# v001.net
KiCad netlist of a schematic drawn in EAGLE
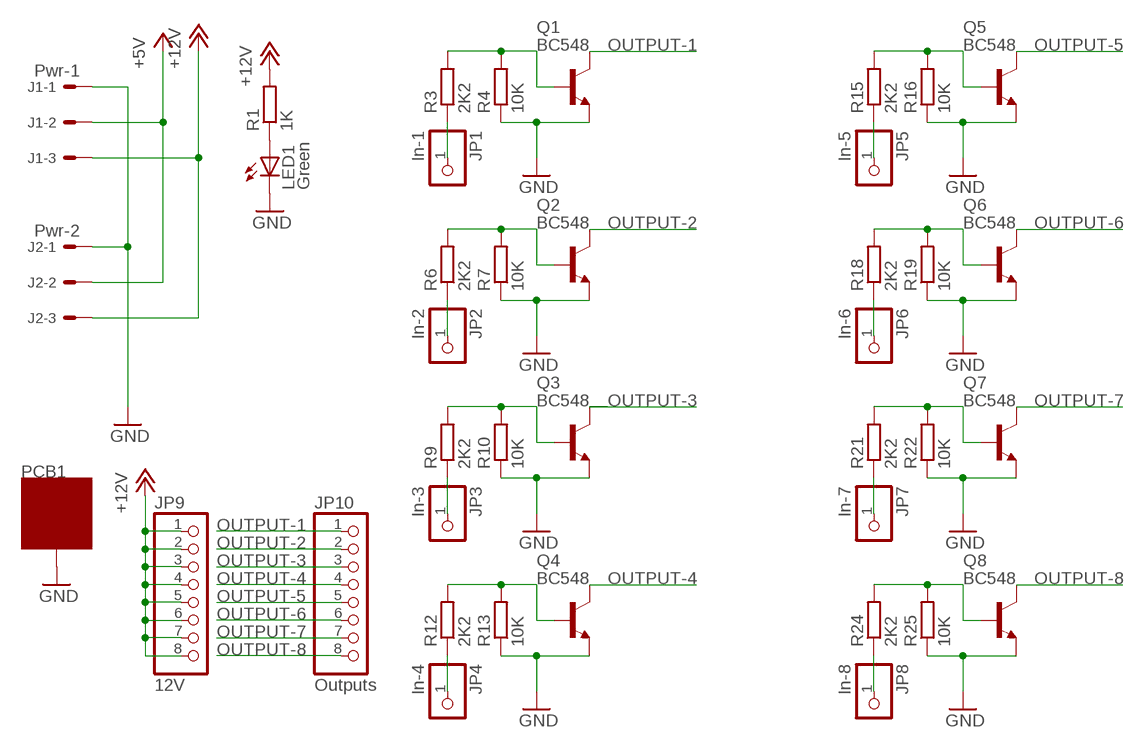
[diagram p0: schematic, sheet 1]

(export (version "E")
  (design (tool "Eeschema 10.0.6"))
  (components
    (comp (ref "J1")
      (value "Pwr-1")
      (footprint "eagle-import:6410-03")
      (libsource (lib "eagle-import") (part "22-?-0327-2031"))
    )
    (comp (ref "J2")
      (value "Pwr-2")
      (footprint "eagle-import:6410-03")
      (libsource (lib "eagle-import") (part "22-?-0327-2031"))
    )
    (comp (ref "JP1")
      (value "In-1")
      (footprint "eagle-import:1X01")
      (libsource (lib "eagle-import") (part "PINHD-1X1"))
    )
    (comp (ref "JP2")
      (value "In-2")
      (footprint "eagle-import:1X01")
      (libsource (lib "eagle-import") (part "PINHD-1X1"))
    )
    (comp (ref "JP3")
      (value "In-3")
      (footprint "eagle-import:1X01")
      (libsource (lib "eagle-import") (part "PINHD-1X1"))
    )
    (comp (ref "JP4")
      (value "In-4")
      (footprint "eagle-import:1X01")
      (libsource (lib "eagle-import") (part "PINHD-1X1"))
    )
    (comp (ref "JP5")
      (value "In-5")
      (footprint "eagle-import:1X01")
      (libsource (lib "eagle-import") (part "PINHD-1X1"))
    )
    (comp (ref "JP6")
      (value "In-6")
      (footprint "eagle-import:1X01")
      (libsource (lib "eagle-import") (part "PINHD-1X1"))
    )
    (comp (ref "JP7")
      (value "In-7")
      (footprint "eagle-import:1X01")
      (libsource (lib "eagle-import") (part "PINHD-1X1"))
    )
    (comp (ref "JP8")
      (value "In-8")
      (footprint "eagle-import:1X01")
      (libsource (lib "eagle-import") (part "PINHD-1X1"))
    )
    (comp (ref "JP9")
      (value "12V")
      (footprint "eagle-import:1X08")
      (libsource (lib "eagle-import") (part "PINHD-1X8"))
    )
    (comp (ref "JP10")
      (value "Outputs")
      (footprint "eagle-import:1X08")
      (libsource (lib "eagle-import") (part "PINHD-1X8"))
    )
    (comp (ref "LED1")
      (value "Green")
      (footprint "eagle-import:LED3MM")
      (libsource (lib "eagle-import") (part "LED3MM"))
    )
    (comp (ref "PCB1")
      (value "ZZZ_MODULE05X05")
      (footprint "eagle-import:ZZZ_MODULE_05X05")
      (libsource (lib "eagle-import") (part "ZZZ_MODULE05X05"))
    )
    (comp (ref "Q1")
      (value "BC548")
      (footprint "eagle-import:TO92-EBC")
      (libsource (lib "eagle-import") (part "BC548"))
    )
    (comp (ref "Q2")
      (value "BC548")
      (footprint "eagle-import:TO92-EBC")
      (libsource (lib "eagle-import") (part "BC548"))
    )
    (comp (ref "Q3")
      (value "BC548")
      (footprint "eagle-import:TO92-EBC")
      (libsource (lib "eagle-import") (part "BC548"))
    )
    (comp (ref "Q4")
      (value "BC548")
      (footprint "eagle-import:TO92-EBC")
      (libsource (lib "eagle-import") (part "BC548"))
    )
    (comp (ref "Q5")
      (value "BC548")
      (footprint "eagle-import:TO92-EBC")
      (libsource (lib "eagle-import") (part "BC548"))
    )
    (comp (ref "Q6")
      (value "BC548")
      (footprint "eagle-import:TO92-EBC")
      (libsource (lib "eagle-import") (part "BC548"))
    )
    (comp (ref "Q7")
      (value "BC548")
      (footprint "eagle-import:TO92-EBC")
      (libsource (lib "eagle-import") (part "BC548"))
    )
    (comp (ref "Q8")
      (value "BC548")
      (footprint "eagle-import:TO92-EBC")
      (libsource (lib "eagle-import") (part "BC548"))
    )
    (comp (ref "R1")
      (value "1K")
      (footprint "eagle-import:0207_2V")
      (libsource (lib "eagle-import") (part "resistor_R-EU_0207/2V"))
    )
    (comp (ref "R3")
      (value "2K2")
      (footprint "eagle-import:0204_7")
      (libsource (lib "eagle-import") (part "R-EU_0204/7"))
    )
    (comp (ref "R4")
      (value "10K")
      (footprint "eagle-import:0207_2V")
      (libsource (lib "eagle-import") (part "resistor_R-EU_0207/2V"))
    )
    (comp (ref "R6")
      (value "2K2")
      (footprint "eagle-import:0204_7")
      (libsource (lib "eagle-import") (part "R-EU_0204/7"))
    )
    (comp (ref "R7")
      (value "10K")
      (footprint "eagle-import:0207_2V")
      (libsource (lib "eagle-import") (part "resistor_R-EU_0207/2V"))
    )
    (comp (ref "R9")
      (value "2K2")
      (footprint "eagle-import:0204_7")
      (libsource (lib "eagle-import") (part "R-EU_0204/7"))
    )
    (comp (ref "R10")
      (value "10K")
      (footprint "eagle-import:0207_2V")
      (libsource (lib "eagle-import") (part "resistor_R-EU_0207/2V"))
    )
    (comp (ref "R12")
      (value "2K2")
      (footprint "eagle-import:0204_7")
      (libsource (lib "eagle-import") (part "R-EU_0204/7"))
    )
    (comp (ref "R13")
      (value "10K")
      (footprint "eagle-import:0207_2V")
      (libsource (lib "eagle-import") (part "resistor_R-EU_0207/2V"))
    )
    (comp (ref "R15")
      (value "2K2")
      (footprint "eagle-import:0204_7")
      (libsource (lib "eagle-import") (part "R-EU_0204/7"))
    )
    (comp (ref "R16")
      (value "10K")
      (footprint "eagle-import:0207_2V")
      (libsource (lib "eagle-import") (part "resistor_R-EU_0207/2V"))
    )
    (comp (ref "R18")
      (value "2K2")
      (footprint "eagle-import:0204_7")
      (libsource (lib "eagle-import") (part "R-EU_0204/7"))
    )
    (comp (ref "R19")
      (value "10K")
      (footprint "eagle-import:0207_2V")
      (libsource (lib "eagle-import") (part "resistor_R-EU_0207/2V"))
    )
    (comp (ref "R21")
      (value "2K2")
      (footprint "eagle-import:0204_7")
      (libsource (lib "eagle-import") (part "R-EU_0204/7"))
    )
    (comp (ref "R22")
      (value "10K")
      (footprint "eagle-import:0207_2V")
      (libsource (lib "eagle-import") (part "resistor_R-EU_0207/2V"))
    )
    (comp (ref "R24")
      (value "2K2")
      (footprint "eagle-import:0204_7")
      (libsource (lib "eagle-import") (part "R-EU_0204/7"))
    )
    (comp (ref "R25")
      (value "10K")
      (footprint "eagle-import:0207_2V")
      (libsource (lib "eagle-import") (part "resistor_R-EU_0207/2V"))
    )
  )
  (nets
    (net (code "1") (name "+5V") (class "Default")
      (node (ref "J1") (pin "2") (pinfunction "S_2") (pintype "passive"))
      (node (ref "J2") (pin "2") (pinfunction "S_2") (pintype "passive"))
    )
    (net (code "2") (name "+12V") (class "Default")
      (node (ref "J1") (pin "3") (pinfunction "S_3") (pintype "passive"))
      (node (ref "J2") (pin "3") (pinfunction "S_3") (pintype "passive"))
      (node (ref "JP9") (pin "1") (pinfunction "1_1") (pintype "passive"))
      (node (ref "JP9") (pin "2") (pinfunction "2_2") (pintype "passive"))
      (node (ref "JP9") (pin "3") (pinfunction "3_3") (pintype "passive"))
      (node (ref "JP9") (pin "4") (pinfunction "4_4") (pintype "passive"))
      (node (ref "JP9") (pin "5") (pinfunction "5_5") (pintype "passive"))
      (node (ref "JP9") (pin "6") (pinfunction "6_6") (pintype "passive"))
      (node (ref "JP9") (pin "7") (pinfunction "7_7") (pintype "passive"))
      (node (ref "JP9") (pin "8") (pinfunction "8_8") (pintype "passive"))
      (node (ref "R1") (pin "2") (pinfunction "2_2") (pintype "passive"))
    )
    (net (code "3") (name "/OUTPUT-1") (class "Default")
      (node (ref "JP10") (pin "1") (pinfunction "1_1") (pintype "passive"))
      (node (ref "Q1") (pin "C") (pinfunction "C_C") (pintype "passive"))
    )
    (net (code "4") (name "/OUTPUT-2") (class "Default")
      (node (ref "JP10") (pin "2") (pinfunction "2_2") (pintype "passive"))
      (node (ref "Q2") (pin "C") (pinfunction "C_C") (pintype "passive"))
    )
    (net (code "5") (name "/OUTPUT-3") (class "Default")
      (node (ref "JP10") (pin "3") (pinfunction "3_3") (pintype "passive"))
      (node (ref "Q3") (pin "C") (pinfunction "C_C") (pintype "passive"))
    )
    (net (code "6") (name "/OUTPUT-4") (class "Default")
      (node (ref "JP10") (pin "4") (pinfunction "4_4") (pintype "passive"))
      (node (ref "Q4") (pin "C") (pinfunction "C_C") (pintype "passive"))
    )
    (net (code "7") (name "/OUTPUT-5") (class "Default")
      (node (ref "JP10") (pin "5") (pinfunction "5_5") (pintype "passive"))
      (node (ref "Q5") (pin "C") (pinfunction "C_C") (pintype "passive"))
    )
    (net (code "8") (name "/OUTPUT-6") (class "Default")
      (node (ref "JP10") (pin "6") (pinfunction "6_6") (pintype "passive"))
      (node (ref "Q6") (pin "C") (pinfunction "C_C") (pintype "passive"))
    )
    (net (code "9") (name "/OUTPUT-7") (class "Default")
      (node (ref "JP10") (pin "7") (pinfunction "7_7") (pintype "passive"))
      (node (ref "Q7") (pin "C") (pinfunction "C_C") (pintype "passive"))
    )
    (net (code "10") (name "/OUTPUT-8") (class "Default")
      (node (ref "JP10") (pin "8") (pinfunction "8_8") (pintype "passive"))
      (node (ref "Q8") (pin "C") (pinfunction "C_C") (pintype "passive"))
    )
    (net (code "11") (name "GND") (class "Default")
      (node (ref "J1") (pin "1") (pinfunction "S_1") (pintype "passive"))
      (node (ref "J2") (pin "1") (pinfunction "S_1") (pintype "passive"))
      (node (ref "LED1") (pin "K") (pinfunction "C_K") (pintype "passive"))
      (node (ref "PCB1") (pin "GND@1") (pinfunction "GND_GND@1") (pintype "power_in"))
      (node (ref "PCB1") (pin "GND@2") (pinfunction "GND_GND@2") (pintype "power_in"))
      (node (ref "PCB1") (pin "GND@3") (pinfunction "GND_GND@3") (pintype "power_in"))
      (node (ref "PCB1") (pin "GND@4") (pinfunction "GND_GND@4") (pintype "power_in"))
      (node (ref "PCB1") (pin "GND@5") (pinfunction "GND_GND@5") (pintype "power_in"))
      (node (ref "PCB1") (pin "GND@6") (pinfunction "GND_GND@6") (pintype "power_in"))
      (node (ref "PCB1") (pin "GND@7") (pinfunction "GND_GND@7") (pintype "power_in"))
      (node (ref "PCB1") (pin "GND@8") (pinfunction "GND_GND@8") (pintype "power_in"))
      (node (ref "Q1") (pin "E") (pinfunction "E_E") (pintype "passive"))
      (node (ref "Q2") (pin "E") (pinfunction "E_E") (pintype "passive"))
      (node (ref "Q3") (pin "E") (pinfunction "E_E") (pintype "passive"))
      (node (ref "Q4") (pin "E") (pinfunction "E_E") (pintype "passive"))
      (node (ref "Q5") (pin "E") (pinfunction "E_E") (pintype "passive"))
      (node (ref "Q6") (pin "E") (pinfunction "E_E") (pintype "passive"))
      (node (ref "Q7") (pin "E") (pinfunction "E_E") (pintype "passive"))
      (node (ref "Q8") (pin "E") (pinfunction "E_E") (pintype "passive"))
      (node (ref "R10") (pin "1") (pinfunction "1_1") (pintype "passive"))
      (node (ref "R13") (pin "1") (pinfunction "1_1") (pintype "passive"))
      (node (ref "R16") (pin "1") (pinfunction "1_1") (pintype "passive"))
      (node (ref "R19") (pin "1") (pinfunction "1_1") (pintype "passive"))
      (node (ref "R22") (pin "1") (pinfunction "1_1") (pintype "passive"))
      (node (ref "R25") (pin "1") (pinfunction "1_1") (pintype "passive"))
      (node (ref "R4") (pin "1") (pinfunction "1_1") (pintype "passive"))
      (node (ref "R7") (pin "1") (pinfunction "1_1") (pintype "passive"))
    )
    (net (code "12") (name "Net-(JP1-Pad1)") (class "Default")
      (node (ref "JP1") (pin "1") (pinfunction "1_1") (pintype "passive"))
      (node (ref "R3") (pin "1") (pinfunction "1_1") (pintype "passive"))
    )
    (net (code "13") (name "Net-(JP2-Pad1)") (class "Default")
      (node (ref "JP2") (pin "1") (pinfunction "1_1") (pintype "passive"))
      (node (ref "R6") (pin "1") (pinfunction "1_1") (pintype "passive"))
    )
    (net (code "14") (name "Net-(JP3-Pad1)") (class "Default")
      (node (ref "JP3") (pin "1") (pinfunction "1_1") (pintype "passive"))
      (node (ref "R9") (pin "1") (pinfunction "1_1") (pintype "passive"))
    )
    (net (code "15") (name "Net-(JP4-Pad1)") (class "Default")
      (node (ref "JP4") (pin "1") (pinfunction "1_1") (pintype "passive"))
      (node (ref "R12") (pin "1") (pinfunction "1_1") (pintype "passive"))
    )
    (net (code "16") (name "Net-(JP5-Pad1)") (class "Default")
      (node (ref "JP5") (pin "1") (pinfunction "1_1") (pintype "passive"))
      (node (ref "R15") (pin "1") (pinfunction "1_1") (pintype "passive"))
    )
    (net (code "17") (name "Net-(JP6-Pad1)") (class "Default")
      (node (ref "JP6") (pin "1") (pinfunction "1_1") (pintype "passive"))
      (node (ref "R18") (pin "1") (pinfunction "1_1") (pintype "passive"))
    )
    (net (code "18") (name "Net-(JP7-Pad1)") (class "Default")
      (node (ref "JP7") (pin "1") (pinfunction "1_1") (pintype "passive"))
      (node (ref "R21") (pin "1") (pinfunction "1_1") (pintype "passive"))
    )
    (net (code "19") (name "Net-(JP8-Pad1)") (class "Default")
      (node (ref "JP8") (pin "1") (pinfunction "1_1") (pintype "passive"))
      (node (ref "R24") (pin "1") (pinfunction "1_1") (pintype "passive"))
    )
    (net (code "20") (name "Net-(LED1-PadA)") (class "Default")
      (node (ref "LED1") (pin "A") (pinfunction "A_A") (pintype "passive"))
      (node (ref "R1") (pin "1") (pinfunction "1_1") (pintype "passive"))
    )
    (net (code "21") (name "Net-(Q1-PadB)") (class "Default")
      (node (ref "Q1") (pin "B") (pinfunction "B_B") (pintype "passive"))
      (node (ref "R3") (pin "2") (pinfunction "2_2") (pintype "passive"))
      (node (ref "R4") (pin "2") (pinfunction "2_2") (pintype "passive"))
    )
    (net (code "22") (name "Net-(Q2-PadB)") (class "Default")
      (node (ref "Q2") (pin "B") (pinfunction "B_B") (pintype "passive"))
      (node (ref "R6") (pin "2") (pinfunction "2_2") (pintype "passive"))
      (node (ref "R7") (pin "2") (pinfunction "2_2") (pintype "passive"))
    )
    (net (code "23") (name "Net-(Q3-PadB)") (class "Default")
      (node (ref "Q3") (pin "B") (pinfunction "B_B") (pintype "passive"))
      (node (ref "R10") (pin "2") (pinfunction "2_2") (pintype "passive"))
      (node (ref "R9") (pin "2") (pinfunction "2_2") (pintype "passive"))
    )
    (net (code "24") (name "Net-(Q4-PadB)") (class "Default")
      (node (ref "Q4") (pin "B") (pinfunction "B_B") (pintype "passive"))
      (node (ref "R12") (pin "2") (pinfunction "2_2") (pintype "passive"))
      (node (ref "R13") (pin "2") (pinfunction "2_2") (pintype "passive"))
    )
    (net (code "25") (name "Net-(Q5-PadB)") (class "Default")
      (node (ref "Q5") (pin "B") (pinfunction "B_B") (pintype "passive"))
      (node (ref "R15") (pin "2") (pinfunction "2_2") (pintype "passive"))
      (node (ref "R16") (pin "2") (pinfunction "2_2") (pintype "passive"))
    )
    (net (code "26") (name "Net-(Q6-PadB)") (class "Default")
      (node (ref "Q6") (pin "B") (pinfunction "B_B") (pintype "passive"))
      (node (ref "R18") (pin "2") (pinfunction "2_2") (pintype "passive"))
      (node (ref "R19") (pin "2") (pinfunction "2_2") (pintype "passive"))
    )
    (net (code "27") (name "Net-(Q7-PadB)") (class "Default")
      (node (ref "Q7") (pin "B") (pinfunction "B_B") (pintype "passive"))
      (node (ref "R21") (pin "2") (pinfunction "2_2") (pintype "passive"))
      (node (ref "R22") (pin "2") (pinfunction "2_2") (pintype "passive"))
    )
    (net (code "28") (name "Net-(Q8-PadB)") (class "Default")
      (node (ref "Q8") (pin "B") (pinfunction "B_B") (pintype "passive"))
      (node (ref "R24") (pin "2") (pinfunction "2_2") (pintype "passive"))
      (node (ref "R25") (pin "2") (pinfunction "2_2") (pintype "passive"))
    )
  )
)
